# game-controller.net
KiCad netlist of a schematic drawn in EAGLE
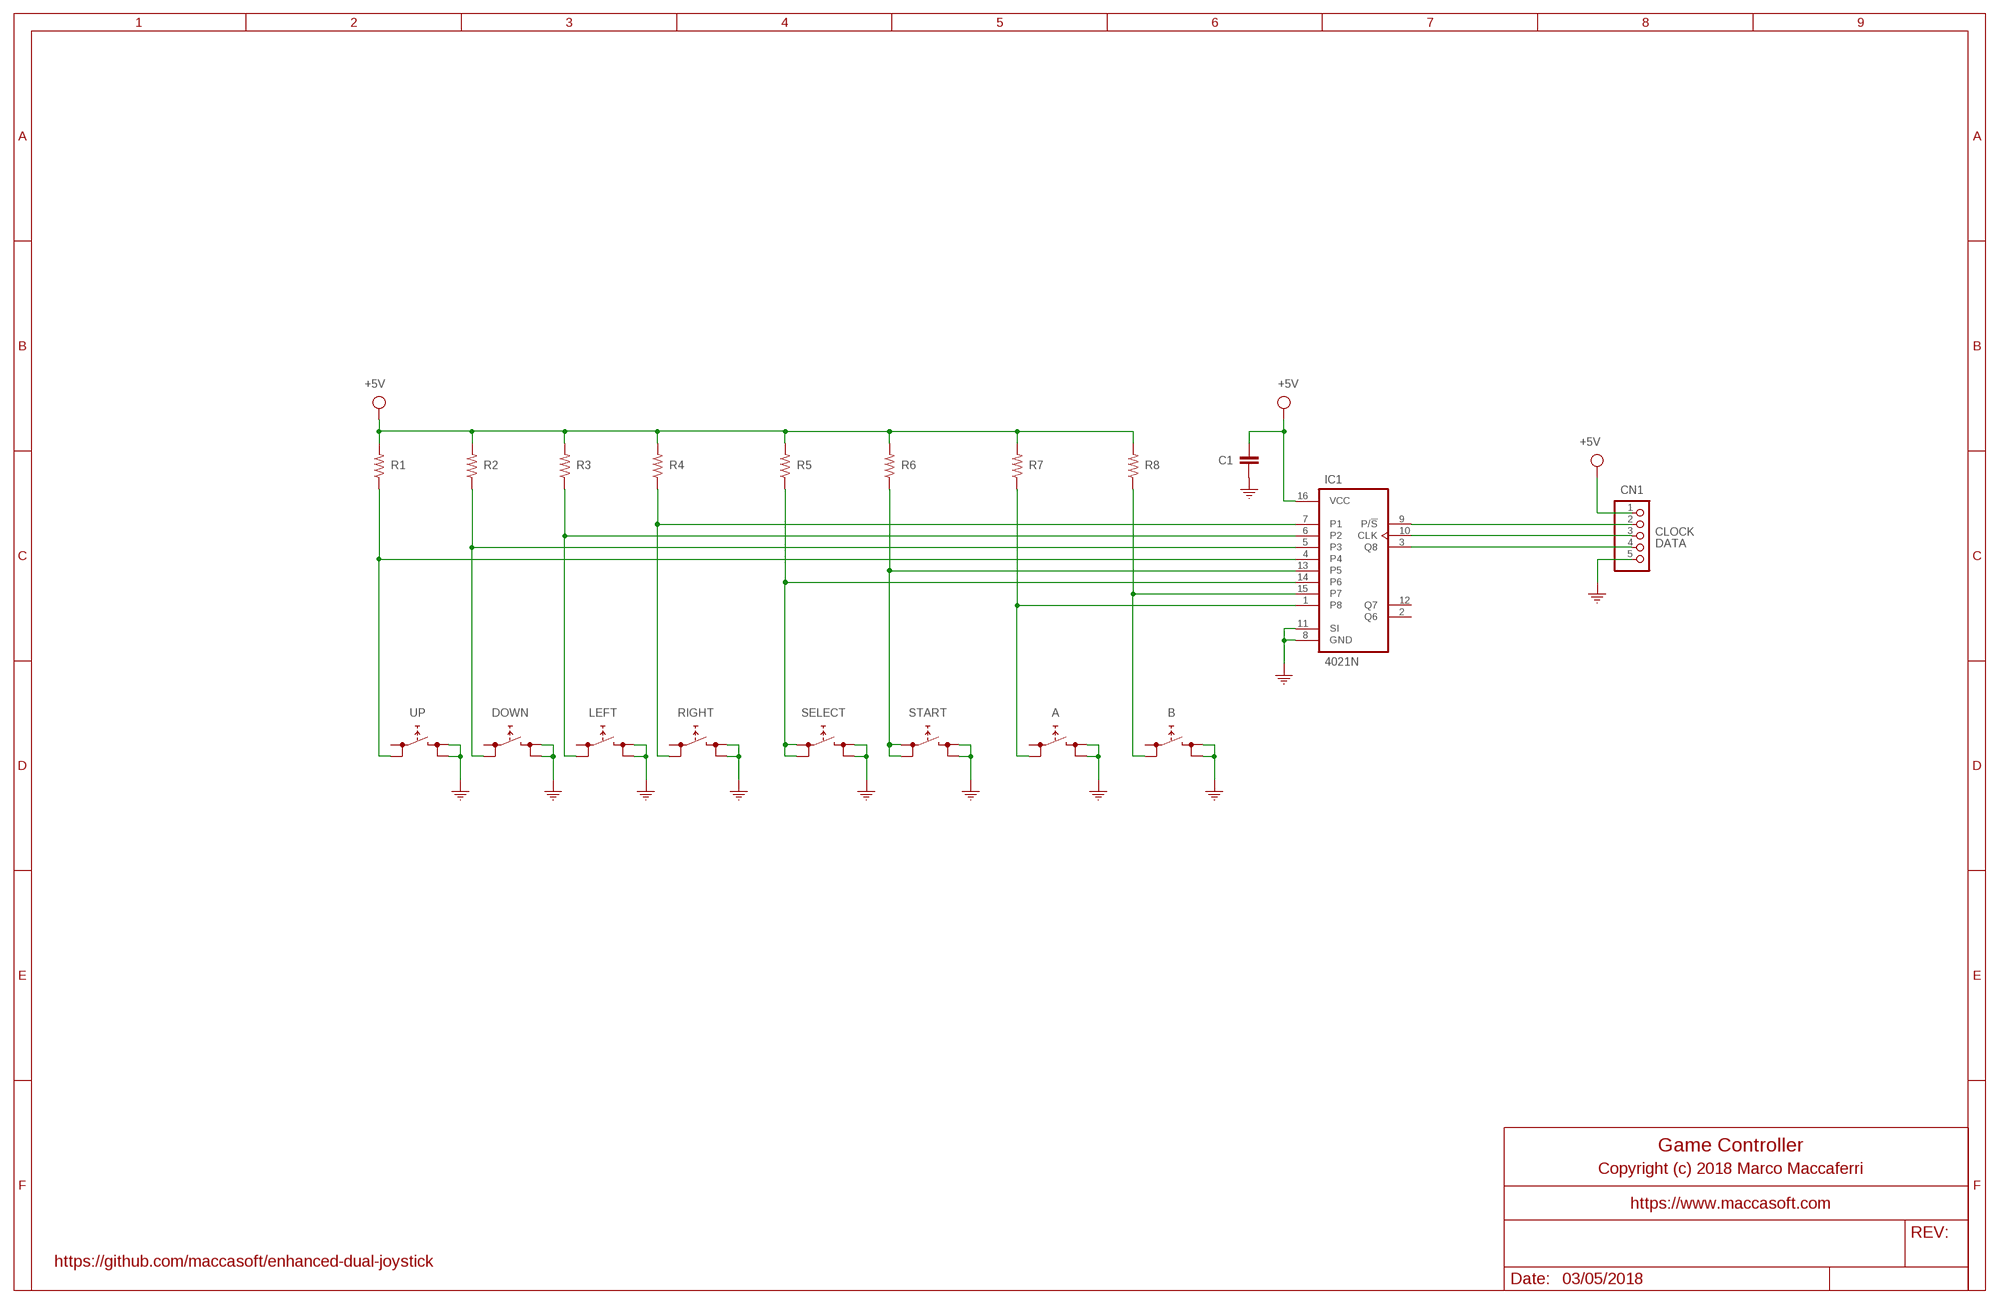
[diagram p0: schematic, sheet 1]

(export (version "E")
  (design (tool "Eeschema 10.0.6"))
  (components
    (comp (ref "A")
      (value "FSM4JH")
      (footprint "eagle-import:TL1105")
      (libsource (lib "eagle-import") (part "BUTTON"))
    )
    (comp (ref "B")
      (value "FSM4JH")
      (footprint "eagle-import:TL1105")
      (libsource (lib "eagle-import") (part "BUTTON"))
    )
    (comp (ref "C1")
      (value "100nF")
      (footprint "eagle-import:C050-025X075")
      (fields (field (name "MPN") "R82EC3100AA70J"))
      (libsource (lib "eagle-import") (part "C"))
    )
    (comp (ref "CN1")
      (value "PINHD-1X5")
      (footprint "eagle-import:1X05")
      (libsource (lib "eagle-import") (part "PINHD-1X5"))
    )
    (comp (ref "DOWN")
      (value "FSM4JH")
      (footprint "eagle-import:TL1105")
      (libsource (lib "eagle-import") (part "BUTTON"))
    )
    (comp (ref "IC1")
      (value "4021N")
      (footprint "eagle-import:DIL16")
      (libsource (lib "eagle-import") (part "4021N"))
    )
    (comp (ref "LEFT")
      (value "FSM4JH")
      (footprint "eagle-import:TL1105")
      (libsource (lib "eagle-import") (part "BUTTON"))
    )
    (comp (ref "R1")
      (value "10K")
      (footprint "eagle-import:0207_10")
      (fields (field (name "MPN") "CFR-25JB-52-10K"))
      (libsource (lib "eagle-import") (part "R-1/4W"))
    )
    (comp (ref "R2")
      (value "10K")
      (footprint "eagle-import:0207_10")
      (fields (field (name "MPN") "CFR-25JB-52-10K"))
      (libsource (lib "eagle-import") (part "R-1/4W"))
    )
    (comp (ref "R3")
      (value "10K")
      (footprint "eagle-import:0207_10")
      (fields (field (name "MPN") "CFR-25JB-52-10K"))
      (libsource (lib "eagle-import") (part "R-1/4W"))
    )
    (comp (ref "R4")
      (value "10K")
      (footprint "eagle-import:0207_10")
      (fields (field (name "MPN") "CFR-25JB-52-10K"))
      (libsource (lib "eagle-import") (part "R-1/4W"))
    )
    (comp (ref "R5")
      (value "10K")
      (footprint "eagle-import:0207_10")
      (fields (field (name "MPN") "CFR-25JB-52-10K"))
      (libsource (lib "eagle-import") (part "R-1/4W"))
    )
    (comp (ref "R6")
      (value "10K")
      (footprint "eagle-import:0207_10")
      (fields (field (name "MPN") "CFR-25JB-52-10K"))
      (libsource (lib "eagle-import") (part "R-1/4W"))
    )
    (comp (ref "R7")
      (value "10K")
      (footprint "eagle-import:0207_10")
      (fields (field (name "MPN") "CFR-25JB-52-10K"))
      (libsource (lib "eagle-import") (part "R-1/4W"))
    )
    (comp (ref "R8")
      (value "10K")
      (footprint "eagle-import:0207_10")
      (fields (field (name "MPN") "CFR-25JB-52-10K"))
      (libsource (lib "eagle-import") (part "R-1/4W"))
    )
    (comp (ref "RIGHT")
      (value "FSM4JH")
      (footprint "eagle-import:TL1105")
      (libsource (lib "eagle-import") (part "BUTTON"))
    )
    (comp (ref "SELECT")
      (value "FSM4JH")
      (footprint "eagle-import:TL1105")
      (libsource (lib "eagle-import") (part "BUTTON"))
    )
    (comp (ref "START")
      (value "FSM4JH")
      (footprint "eagle-import:TL1105")
      (libsource (lib "eagle-import") (part "BUTTON"))
    )
    (comp (ref "UP")
      (value "FSM4JH")
      (footprint "eagle-import:TL1105")
      (libsource (lib "eagle-import") (part "BUTTON"))
    )
  )
  (nets
    (net (code "1") (name "+5V") (class "Default")
      (node (ref "C1") (pin "1") (pinfunction "1_1") (pintype "passive"))
      (node (ref "CN1") (pin "1") (pinfunction "1_1") (pintype "passive"))
      (node (ref "IC1") (pin "16") (pinfunction "VCC_16") (pintype "power_in"))
      (node (ref "R1") (pin "2") (pinfunction "2_2") (pintype "passive"))
      (node (ref "R2") (pin "2") (pinfunction "2_2") (pintype "passive"))
      (node (ref "R3") (pin "2") (pinfunction "2_2") (pintype "passive"))
      (node (ref "R4") (pin "2") (pinfunction "2_2") (pintype "passive"))
      (node (ref "R5") (pin "2") (pinfunction "2_2") (pintype "passive"))
      (node (ref "R6") (pin "2") (pinfunction "2_2") (pintype "passive"))
      (node (ref "R7") (pin "2") (pinfunction "2_2") (pintype "passive"))
      (node (ref "R8") (pin "2") (pinfunction "2_2") (pintype "passive"))
    )
    (net (code "2") (name "/CLOCK") (class "Default")
      (node (ref "CN1") (pin "3") (pinfunction "3_3") (pintype "passive"))
      (node (ref "IC1") (pin "10") (pinfunction "CLK_10") (pintype "input"))
    )
    (net (code "3") (name "/DATA") (class "Default")
      (node (ref "CN1") (pin "4") (pinfunction "4_4") (pintype "passive"))
      (node (ref "IC1") (pin "3") (pinfunction "Q8_3") (pintype "output"))
    )
    (net (code "4") (name "GND") (class "Default")
      (node (ref "A") (pin "2") (pinfunction "1_2") (pintype "passive"))
      (node (ref "A") (pin "4") (pinfunction "1_4") (pintype "passive"))
      (node (ref "B") (pin "2") (pinfunction "1_2") (pintype "passive"))
      (node (ref "B") (pin "4") (pinfunction "1_4") (pintype "passive"))
      (node (ref "C1") (pin "2") (pinfunction "2_2") (pintype "passive"))
      (node (ref "CN1") (pin "5") (pinfunction "5_5") (pintype "passive"))
      (node (ref "DOWN") (pin "2") (pinfunction "1_2") (pintype "passive"))
      (node (ref "DOWN") (pin "4") (pinfunction "1_4") (pintype "passive"))
      (node (ref "IC1") (pin "11") (pinfunction "SI_11") (pintype "input"))
      (node (ref "IC1") (pin "8") (pinfunction "GND_8") (pintype "power_in"))
      (node (ref "LEFT") (pin "2") (pinfunction "1_2") (pintype "passive"))
      (node (ref "LEFT") (pin "4") (pinfunction "1_4") (pintype "passive"))
      (node (ref "RIGHT") (pin "2") (pinfunction "1_2") (pintype "passive"))
      (node (ref "RIGHT") (pin "4") (pinfunction "1_4") (pintype "passive"))
      (node (ref "SELECT") (pin "2") (pinfunction "1_2") (pintype "passive"))
      (node (ref "SELECT") (pin "4") (pinfunction "1_4") (pintype "passive"))
      (node (ref "START") (pin "2") (pinfunction "1_2") (pintype "passive"))
      (node (ref "START") (pin "4") (pinfunction "1_4") (pintype "passive"))
      (node (ref "UP") (pin "2") (pinfunction "1_2") (pintype "passive"))
      (node (ref "UP") (pin "4") (pinfunction "1_4") (pintype "passive"))
    )
    (net (code "5") (name "Net-(IC1-P1)") (class "Default")
      (node (ref "IC1") (pin "7") (pinfunction "P1_7") (pintype "input"))
      (node (ref "R4") (pin "1") (pinfunction "1_1") (pintype "passive"))
      (node (ref "RIGHT") (pin "3") (pinfunction "0_3") (pintype "passive"))
    )
    (net (code "6") (name "Net-(IC1-P2)") (class "Default")
      (node (ref "IC1") (pin "6") (pinfunction "P2_6") (pintype "input"))
      (node (ref "LEFT") (pin "3") (pinfunction "0_3") (pintype "passive"))
      (node (ref "R3") (pin "1") (pinfunction "1_1") (pintype "passive"))
    )
    (net (code "7") (name "Net-(IC1-P3)") (class "Default")
      (node (ref "DOWN") (pin "3") (pinfunction "0_3") (pintype "passive"))
      (node (ref "IC1") (pin "5") (pinfunction "P3_5") (pintype "input"))
      (node (ref "R2") (pin "1") (pinfunction "1_1") (pintype "passive"))
    )
    (net (code "8") (name "Net-(IC1-P4)") (class "Default")
      (node (ref "IC1") (pin "4") (pinfunction "P4_4") (pintype "input"))
      (node (ref "R1") (pin "1") (pinfunction "1_1") (pintype "passive"))
      (node (ref "UP") (pin "3") (pinfunction "0_3") (pintype "passive"))
    )
    (net (code "9") (name "Net-(IC1-P5)") (class "Default")
      (node (ref "IC1") (pin "13") (pinfunction "P5_13") (pintype "input"))
      (node (ref "R6") (pin "1") (pinfunction "1_1") (pintype "passive"))
      (node (ref "START") (pin "1") (pinfunction "0_1") (pintype "passive"))
      (node (ref "START") (pin "3") (pinfunction "0_3") (pintype "passive"))
    )
    (net (code "10") (name "Net-(IC1-P6)") (class "Default")
      (node (ref "IC1") (pin "14") (pinfunction "P6_14") (pintype "input"))
      (node (ref "R5") (pin "1") (pinfunction "1_1") (pintype "passive"))
      (node (ref "SELECT") (pin "1") (pinfunction "0_1") (pintype "passive"))
      (node (ref "SELECT") (pin "3") (pinfunction "0_3") (pintype "passive"))
    )
    (net (code "11") (name "Net-(IC1-P7)") (class "Default")
      (node (ref "B") (pin "3") (pinfunction "0_3") (pintype "passive"))
      (node (ref "IC1") (pin "15") (pinfunction "P7_15") (pintype "input"))
      (node (ref "R8") (pin "1") (pinfunction "1_1") (pintype "passive"))
    )
    (net (code "12") (name "Net-(IC1-P8)") (class "Default")
      (node (ref "A") (pin "3") (pinfunction "0_3") (pintype "passive"))
      (node (ref "IC1") (pin "1") (pinfunction "P8_1") (pintype "input"))
      (node (ref "R7") (pin "1") (pinfunction "1_1") (pintype "passive"))
    )
    (net (code "13") (name "Net-(IC1-P{slash}~{S})") (class "Default")
      (node (ref "CN1") (pin "2") (pinfunction "2_2") (pintype "passive"))
      (node (ref "IC1") (pin "9") (pinfunction "P/~{S}_9") (pintype "input"))
    )
    (net (code "14") (name "unconnected-(A-0-Pad1)") (class "Default")
      (node (ref "A") (pin "1") (pinfunction "0_1") (pintype "passive"))
    )
    (net (code "15") (name "unconnected-(B-0-Pad1)") (class "Default")
      (node (ref "B") (pin "1") (pinfunction "0_1") (pintype "passive"))
    )
    (net (code "16") (name "unconnected-(DOWN-0-Pad1)") (class "Default")
      (node (ref "DOWN") (pin "1") (pinfunction "0_1") (pintype "passive"))
    )
    (net (code "17") (name "unconnected-(IC1-Q6-Pad2)") (class "Default")
      (node (ref "IC1") (pin "2") (pinfunction "Q6_2") (pintype "output"))
    )
    (net (code "18") (name "unconnected-(IC1-Q7-Pad12)") (class "Default")
      (node (ref "IC1") (pin "12") (pinfunction "Q7_12") (pintype "output"))
    )
    (net (code "19") (name "unconnected-(LEFT-0-Pad1)") (class "Default")
      (node (ref "LEFT") (pin "1") (pinfunction "0_1") (pintype "passive"))
    )
    (net (code "20") (name "unconnected-(RIGHT-0-Pad1)") (class "Default")
      (node (ref "RIGHT") (pin "1") (pinfunction "0_1") (pintype "passive"))
    )
    (net (code "21") (name "unconnected-(UP-0-Pad1)") (class "Default")
      (node (ref "UP") (pin "1") (pinfunction "0_1") (pintype "passive"))
    )
  )
)
